# Sheet1.net
KiCad netlist of a schematic drawn in Altium Designer
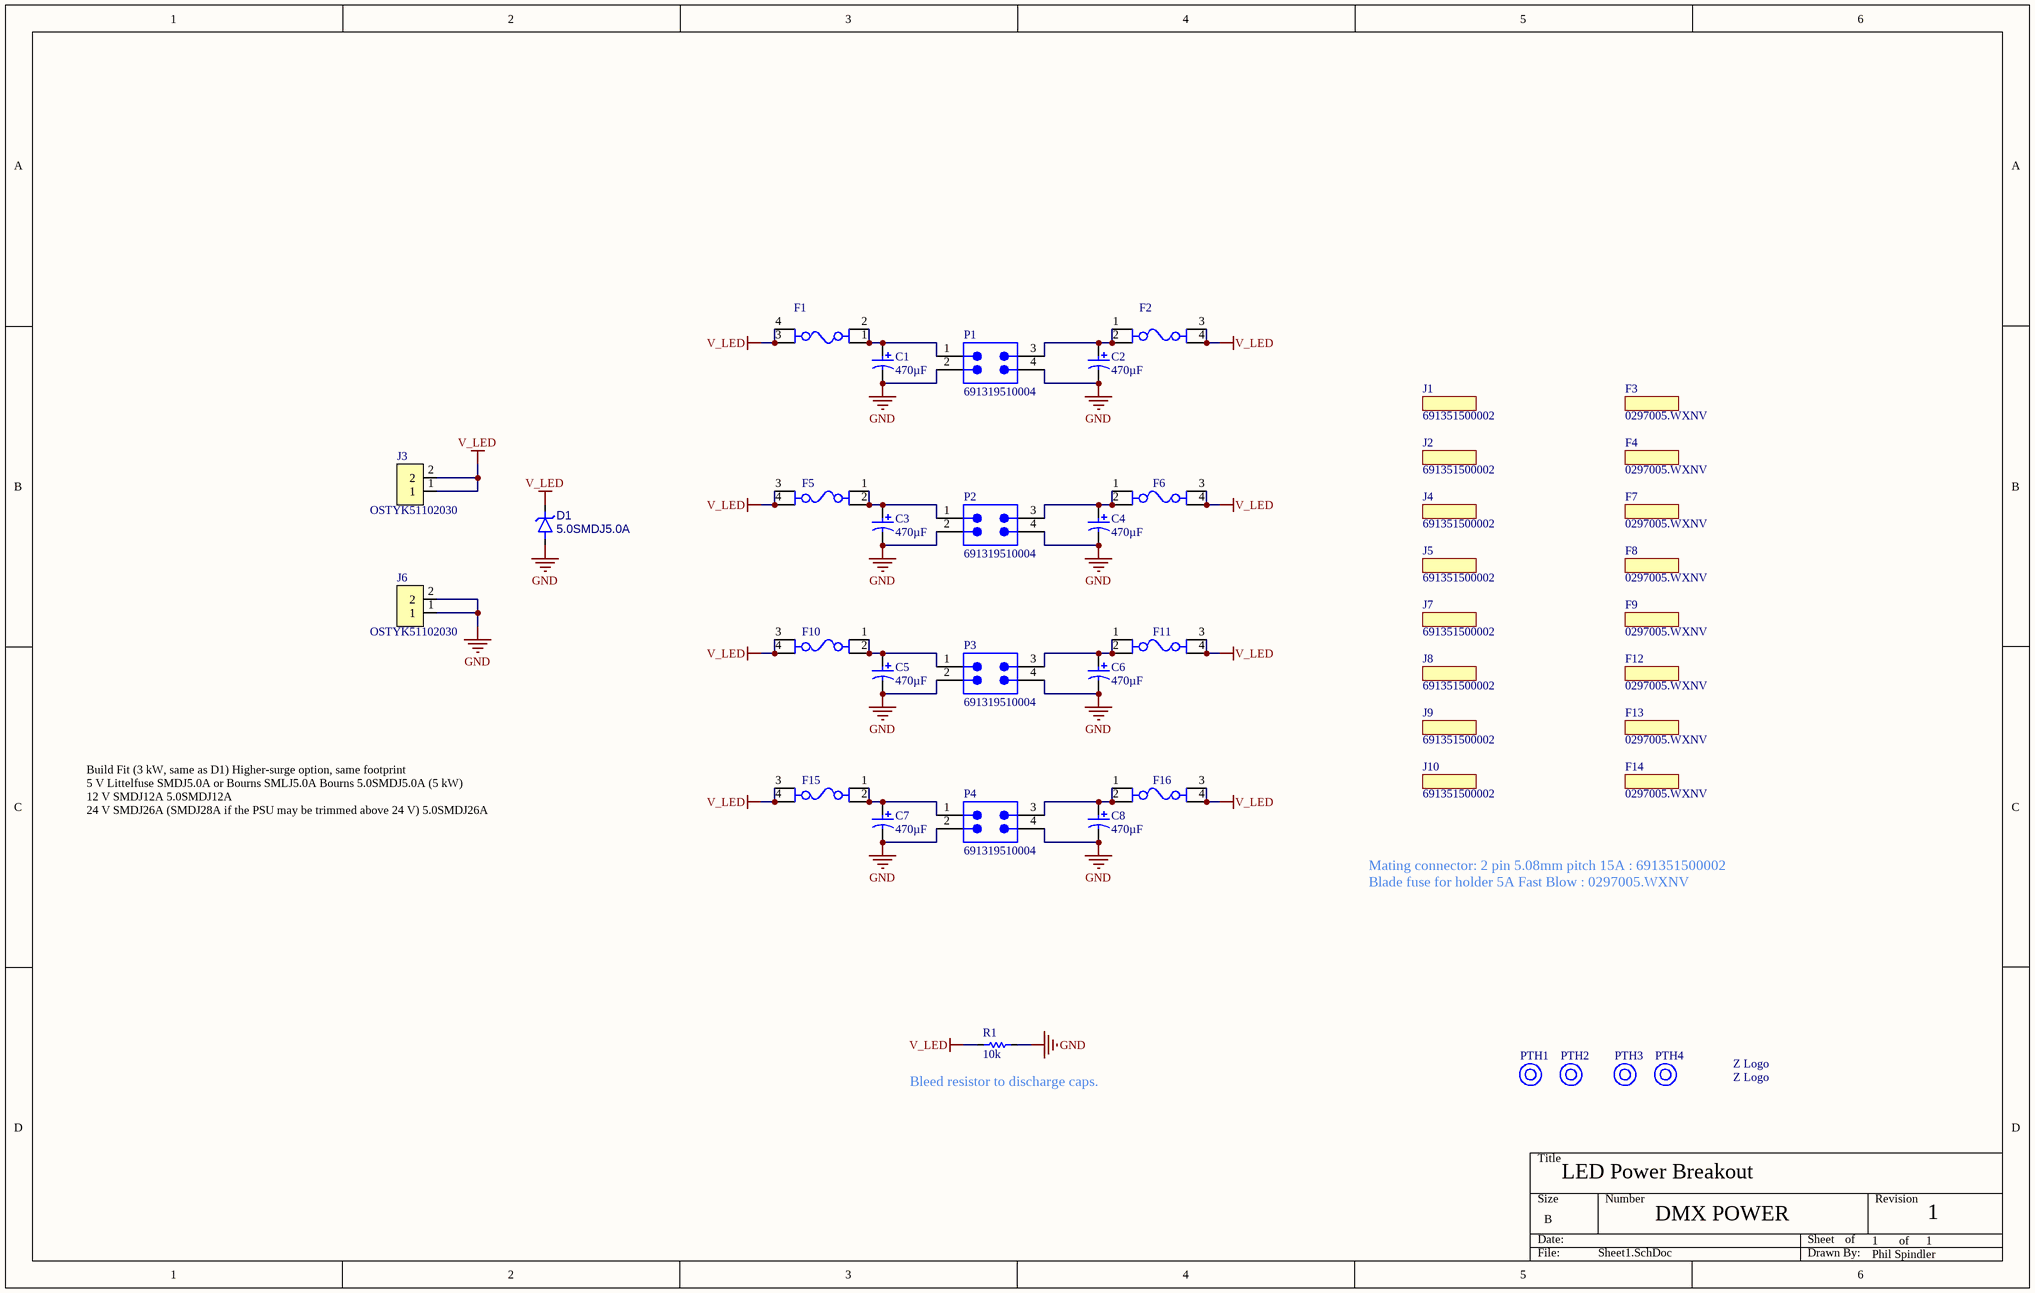
[diagram p0: Sheet1.SchDoc]

(export (version "E")
  (design (tool "Eeschema 10.0.6"))
  (components
    (comp (ref "C1")
      (value "470µF")
      (footprint "CAP_POL_DIAM10_H22_SPACING5")
      (description "CAP ALUM 470UF 20% 50V RADIAL TH")
      (fields (field (name "TOLERANCE") "20%") (field (name "Comment") "REH1020471M050K"))
      (libsource (lib "Equus Computer Systems") (part "CAP-P-2"))
    )
    (comp (ref "C2")
      (value "470µF")
      (footprint "CAP_POL_DIAM10_H22_SPACING5")
      (description "CAP ALUM 470UF 20% 50V RADIAL TH")
      (fields (field (name "TOLERANCE") "20%") (field (name "Comment") "REH1020471M050K"))
      (libsource (lib "Equus Computer Systems") (part "CAP-P-2"))
    )
    (comp (ref "C3")
      (value "470µF")
      (footprint "CAP_POL_DIAM10_H22_SPACING5")
      (description "CAP ALUM 470UF 20% 50V RADIAL TH")
      (fields (field (name "TOLERANCE") "20%") (field (name "Comment") "REH1020471M050K"))
      (libsource (lib "Equus Computer Systems") (part "CAP-P-2"))
    )
    (comp (ref "C4")
      (value "470µF")
      (footprint "CAP_POL_DIAM10_H22_SPACING5")
      (description "CAP ALUM 470UF 20% 50V RADIAL TH")
      (fields (field (name "TOLERANCE") "20%") (field (name "Comment") "REH1020471M050K"))
      (libsource (lib "Equus Computer Systems") (part "CAP-P-2"))
    )
    (comp (ref "C5")
      (value "470µF")
      (footprint "CAP_POL_DIAM10_H22_SPACING5")
      (description "CAP ALUM 470UF 20% 50V RADIAL TH")
      (fields (field (name "TOLERANCE") "20%") (field (name "Comment") "REH1020471M050K"))
      (libsource (lib "Equus Computer Systems") (part "CAP-P-2"))
    )
    (comp (ref "C6")
      (value "470µF")
      (footprint "CAP_POL_DIAM10_H22_SPACING5")
      (description "CAP ALUM 470UF 20% 50V RADIAL TH")
      (fields (field (name "TOLERANCE") "20%") (field (name "Comment") "REH1020471M050K"))
      (libsource (lib "Equus Computer Systems") (part "CAP-P-2"))
    )
    (comp (ref "C7")
      (value "470µF")
      (footprint "CAP_POL_DIAM10_H22_SPACING5")
      (description "CAP ALUM 470UF 20% 50V RADIAL TH")
      (fields (field (name "TOLERANCE") "20%") (field (name "Comment") "REH1020471M050K"))
      (libsource (lib "Equus Computer Systems") (part "CAP-P-2"))
    )
    (comp (ref "C8")
      (value "470µF")
      (footprint "CAP_POL_DIAM10_H22_SPACING5")
      (description "CAP ALUM 470UF 20% 50V RADIAL TH")
      (fields (field (name "TOLERANCE") "20%") (field (name "Comment") "REH1020471M050K"))
      (libsource (lib "Equus Computer Systems") (part "CAP-P-2"))
    )
    (comp (ref "D1")
      (value "5.0SMDJ5.0A")
      (footprint "SMDJ_DO-214AB")
      (description "5V Unidirectional 5kW TVS Diode, 9.2V Vwm, 6.4V Vbr, SMC(DO-214AB), SMD")
      (libsource (lib "Equus Computer Systems") (part "DIODE-TVS-2"))
    )
    (comp (ref "F1")
      (value "3544-2")
      (footprint "3544-2-Footprint-1")
      (description "Auto blade fuse holder; for 2.8x0.8mm mini blade fuses ATM; 20A; THT")
      (libsource (lib "Equus Computer Systems") (part "3568"))
    )
    (comp (ref "F2")
      (value "3544-2")
      (footprint "3544-2-Footprint-1")
      (description "Auto blade fuse holder; for 2.8x0.8mm mini blade fuses ATM; 20A; THT")
      (libsource (lib "Equus Computer Systems") (part "3568"))
    )
    (comp (ref "F3")
      (value "0297005.WXNV")
      (footprint "FP-0297-MFG")
      (description "Fuse Blade 5A 32V Socket 10.9 X 3.8 X 8.8mm Polyamide 66 Automotive UL")
      (libsource (lib "Equus Computer Systems") (part "MatingPartForBom"))
    )
    (comp (ref "F4")
      (value "0297005.WXNV")
      (footprint "FP-0297-MFG")
      (description "Fuse Blade 5A 32V Socket 10.9 X 3.8 X 8.8mm Polyamide 66 Automotive UL")
      (libsource (lib "Equus Computer Systems") (part "MatingPartForBom"))
    )
    (comp (ref "F5")
      (value "3544-2")
      (footprint "3544-2-Footprint-1")
      (description "Auto blade fuse holder; for 2.8x0.8mm mini blade fuses ATM; 20A; THT")
      (libsource (lib "Equus Computer Systems") (part "3568"))
    )
    (comp (ref "F6")
      (value "3544-2")
      (footprint "3544-2-Footprint-1")
      (description "Auto blade fuse holder; for 2.8x0.8mm mini blade fuses ATM; 20A; THT")
      (libsource (lib "Equus Computer Systems") (part "3568"))
    )
    (comp (ref "F7")
      (value "0297005.WXNV")
      (footprint "FP-0297-MFG")
      (description "Fuse Blade 5A 32V Socket 10.9 X 3.8 X 8.8mm Polyamide 66 Automotive UL")
      (libsource (lib "Equus Computer Systems") (part "MatingPartForBom"))
    )
    (comp (ref "F8")
      (value "0297005.WXNV")
      (footprint "FP-0297-MFG")
      (description "Fuse Blade 5A 32V Socket 10.9 X 3.8 X 8.8mm Polyamide 66 Automotive UL")
      (libsource (lib "Equus Computer Systems") (part "MatingPartForBom"))
    )
    (comp (ref "F9")
      (value "0297005.WXNV")
      (footprint "FP-0297-MFG")
      (description "Fuse Blade 5A 32V Socket 10.9 X 3.8 X 8.8mm Polyamide 66 Automotive UL")
      (libsource (lib "Equus Computer Systems") (part "MatingPartForBom"))
    )
    (comp (ref "F10")
      (value "3544-2")
      (footprint "3544-2-Footprint-1")
      (description "Auto blade fuse holder; for 2.8x0.8mm mini blade fuses ATM; 20A; THT")
      (libsource (lib "Equus Computer Systems") (part "3568"))
    )
    (comp (ref "F11")
      (value "3544-2")
      (footprint "3544-2-Footprint-1")
      (description "Auto blade fuse holder; for 2.8x0.8mm mini blade fuses ATM; 20A; THT")
      (libsource (lib "Equus Computer Systems") (part "3568"))
    )
    (comp (ref "F12")
      (value "0297005.WXNV")
      (footprint "FP-0297-MFG")
      (description "Fuse Blade 5A 32V Socket 10.9 X 3.8 X 8.8mm Polyamide 66 Automotive UL")
      (libsource (lib "Equus Computer Systems") (part "MatingPartForBom"))
    )
    (comp (ref "F13")
      (value "0297005.WXNV")
      (footprint "FP-0297-MFG")
      (description "Fuse Blade 5A 32V Socket 10.9 X 3.8 X 8.8mm Polyamide 66 Automotive UL")
      (libsource (lib "Equus Computer Systems") (part "MatingPartForBom"))
    )
    (comp (ref "F14")
      (value "0297005.WXNV")
      (footprint "FP-0297-MFG")
      (description "Fuse Blade 5A 32V Socket 10.9 X 3.8 X 8.8mm Polyamide 66 Automotive UL")
      (libsource (lib "Equus Computer Systems") (part "MatingPartForBom"))
    )
    (comp (ref "F15")
      (value "3544-2")
      (footprint "3544-2-Footprint-1")
      (description "Auto blade fuse holder; for 2.8x0.8mm mini blade fuses ATM; 20A; THT")
      (libsource (lib "Equus Computer Systems") (part "3568"))
    )
    (comp (ref "F16")
      (value "3544-2")
      (footprint "3544-2-Footprint-1")
      (description "Auto blade fuse holder; for 2.8x0.8mm mini blade fuses ATM; 20A; THT")
      (libsource (lib "Equus Computer Systems") (part "3568"))
    )
    (comp (ref "J1")
      (value "691351500002")
      (footprint "691351500002-Footprint-1")
      (description "Terminal Block, Pluggable, 2Pos, 12Awg;")
      (libsource (lib "Equus Computer Systems") (part "MatingPartForBom"))
    )
    (comp (ref "J2")
      (value "691351500002")
      (footprint "691351500002-Footprint-1")
      (description "Terminal Block, Pluggable, 2Pos, 12Awg;")
      (libsource (lib "Equus Computer Systems") (part "MatingPartForBom"))
    )
    (comp (ref "J3")
      (value "OSTYK51102030")
      (footprint "OSTYK51102030-Footprint-1")
      (description "Conn Terminal Block 2 POS 9.5mm Solder ST Thru-Hole 30A")
      (libsource (lib "Equus Computer Systems") (part "HEADER-2x1"))
    )
    (comp (ref "J4")
      (value "691351500002")
      (footprint "691351500002-Footprint-1")
      (description "Terminal Block, Pluggable, 2Pos, 12Awg;")
      (libsource (lib "Equus Computer Systems") (part "MatingPartForBom"))
    )
    (comp (ref "J5")
      (value "691351500002")
      (footprint "691351500002-Footprint-1")
      (description "Terminal Block, Pluggable, 2Pos, 12Awg;")
      (libsource (lib "Equus Computer Systems") (part "MatingPartForBom"))
    )
    (comp (ref "J6")
      (value "OSTYK51102030")
      (footprint "OSTYK51102030-Footprint-1")
      (description "Conn Terminal Block 2 POS 9.5mm Solder ST Thru-Hole 30A")
      (libsource (lib "Equus Computer Systems") (part "HEADER-2x1"))
    )
    (comp (ref "J7")
      (value "691351500002")
      (footprint "691351500002-Footprint-1")
      (description "Terminal Block, Pluggable, 2Pos, 12Awg;")
      (libsource (lib "Equus Computer Systems") (part "MatingPartForBom"))
    )
    (comp (ref "J8")
      (value "691351500002")
      (footprint "691351500002-Footprint-1")
      (description "Terminal Block, Pluggable, 2Pos, 12Awg;")
      (libsource (lib "Equus Computer Systems") (part "MatingPartForBom"))
    )
    (comp (ref "J9")
      (value "691351500002")
      (footprint "691351500002-Footprint-1")
      (description "Terminal Block, Pluggable, 2Pos, 12Awg;")
      (libsource (lib "Equus Computer Systems") (part "MatingPartForBom"))
    )
    (comp (ref "J10")
      (value "691351500002")
      (footprint "691351500002-Footprint-1")
      (description "Terminal Block, Pluggable, 2Pos, 12Awg;")
      (libsource (lib "Equus Computer Systems") (part "MatingPartForBom"))
    )
    (comp (ref "P1")
      (value "691319510004")
      (footprint "691319510004")
      (description "Terminal Block, 5.08MM, Dbl Lvl Horizontal Male Pcb Header W/closed Flange, 4PI")
      (libsource (lib "Equus Computer Systems") (part "TBL - 2R - 04P - Male"))
    )
    (comp (ref "P2")
      (value "691319510004")
      (footprint "691319510004")
      (description "Terminal Block, 5.08MM, Dbl Lvl Horizontal Male Pcb Header W/closed Flange, 4PI")
      (libsource (lib "Equus Computer Systems") (part "TBL - 2R - 04P - Male"))
    )
    (comp (ref "P3")
      (value "691319510004")
      (footprint "691319510004")
      (description "Terminal Block, 5.08MM, Dbl Lvl Horizontal Male Pcb Header W/closed Flange, 4PI")
      (libsource (lib "Equus Computer Systems") (part "TBL - 2R - 04P - Male"))
    )
    (comp (ref "P4")
      (value "691319510004")
      (footprint "691319510004")
      (description "Terminal Block, 5.08MM, Dbl Lvl Horizontal Male Pcb Header W/closed Flange, 4PI")
      (libsource (lib "Equus Computer Systems") (part "TBL - 2R - 04P - Male"))
    )
    (comp (ref "PTH1")
      (value "Mounting Hole NPTH")
      (footprint "Mounting Hole M3 No Washer NPTH")
      (libsource (lib "Equus Computer Systems") (part "Mounting Hole NPTH"))
    )
    (comp (ref "PTH2")
      (value "Mounting Hole NPTH")
      (footprint "Mounting Hole M3 No Washer NPTH")
      (libsource (lib "Equus Computer Systems") (part "Mounting Hole NPTH"))
    )
    (comp (ref "PTH3")
      (value "Mounting Hole NPTH")
      (footprint "Mounting Hole M3 No Washer NPTH")
      (libsource (lib "Equus Computer Systems") (part "Mounting Hole NPTH"))
    )
    (comp (ref "PTH4")
      (value "Mounting Hole NPTH")
      (footprint "Mounting Hole M3 No Washer NPTH")
      (libsource (lib "Equus Computer Systems") (part "Mounting Hole NPTH"))
    )
    (comp (ref "R1")
      (value "10k")
      (footprint "RESC3116X06N_1206MED")
      (fields
        (field (name "POWER") "250mW")
        (field (name "TOLERANCE") "1%")
        (field (name "Comment") "RC1206FR-0710KL")
      )
      (libsource (lib "Equus Computer Systems") (part "RES-2"))
    )
    (comp (ref "_1")
      (value "Z Logo")
      (footprint "Z Logo 0.5\"")
      (description "Z logo silkscreen")
      (libsource (lib "Equus Computer Systems") (part "Z Logo"))
    )
  )
  (nets
    (net (code "1") (name "GND") (class "Default")
      (node (ref "C1") (pin "2") (pinfunction "2_2") (pintype "passive"))
      (node (ref "C2") (pin "2") (pinfunction "2_2") (pintype "passive"))
      (node (ref "C3") (pin "2") (pinfunction "2_2") (pintype "passive"))
      (node (ref "C4") (pin "2") (pinfunction "2_2") (pintype "passive"))
      (node (ref "C5") (pin "2") (pinfunction "2_2") (pintype "passive"))
      (node (ref "C6") (pin "2") (pinfunction "2_2") (pintype "passive"))
      (node (ref "C7") (pin "2") (pinfunction "2_2") (pintype "passive"))
      (node (ref "C8") (pin "2") (pinfunction "2_2") (pintype "passive"))
      (node (ref "D1") (pin "2") (pinfunction "A_2") (pintype "passive"))
      (node (ref "J6") (pin "1") (pinfunction "1_1") (pintype "passive"))
      (node (ref "J6") (pin "2") (pinfunction "2_2") (pintype "passive"))
      (node (ref "P1") (pin "2") (pinfunction "2_2") (pintype "passive"))
      (node (ref "P1") (pin "4") (pinfunction "4_4") (pintype "passive"))
      (node (ref "P2") (pin "2") (pinfunction "2_2") (pintype "passive"))
      (node (ref "P2") (pin "4") (pinfunction "4_4") (pintype "passive"))
      (node (ref "P3") (pin "2") (pinfunction "2_2") (pintype "passive"))
      (node (ref "P3") (pin "4") (pinfunction "4_4") (pintype "passive"))
      (node (ref "P4") (pin "2") (pinfunction "2_2") (pintype "passive"))
      (node (ref "P4") (pin "4") (pinfunction "4_4") (pintype "passive"))
      (node (ref "R1") (pin "2") (pinfunction "2_2") (pintype "passive"))
    )
    (net (code "2") (name "Net-(C1-Pad1)") (class "Default")
      (node (ref "C1") (pin "1") (pinfunction "1_1") (pintype "passive"))
      (node (ref "F1") (pin "1") (pinfunction "1_1") (pintype "passive"))
      (node (ref "F1") (pin "2") (pinfunction "2_2") (pintype "passive"))
      (node (ref "P1") (pin "1") (pinfunction "1_1") (pintype "passive"))
    )
    (net (code "3") (name "Net-(C2-Pad1)") (class "Default")
      (node (ref "C2") (pin "1") (pinfunction "1_1") (pintype "passive"))
      (node (ref "F2") (pin "1") (pinfunction "1_1") (pintype "passive"))
      (node (ref "F2") (pin "2") (pinfunction "2_2") (pintype "passive"))
      (node (ref "P1") (pin "3") (pinfunction "3_3") (pintype "passive"))
    )
    (net (code "4") (name "Net-(C3-Pad1)") (class "Default")
      (node (ref "C3") (pin "1") (pinfunction "1_1") (pintype "passive"))
      (node (ref "F5") (pin "1") (pinfunction "1_1") (pintype "passive"))
      (node (ref "F5") (pin "2") (pinfunction "2_2") (pintype "passive"))
      (node (ref "P2") (pin "1") (pinfunction "1_1") (pintype "passive"))
    )
    (net (code "5") (name "Net-(C4-Pad1)") (class "Default")
      (node (ref "C4") (pin "1") (pinfunction "1_1") (pintype "passive"))
      (node (ref "F6") (pin "1") (pinfunction "1_1") (pintype "passive"))
      (node (ref "F6") (pin "2") (pinfunction "2_2") (pintype "passive"))
      (node (ref "P2") (pin "3") (pinfunction "3_3") (pintype "passive"))
    )
    (net (code "6") (name "Net-(C5-Pad1)") (class "Default")
      (node (ref "C5") (pin "1") (pinfunction "1_1") (pintype "passive"))
      (node (ref "F10") (pin "1") (pinfunction "1_1") (pintype "passive"))
      (node (ref "F10") (pin "2") (pinfunction "2_2") (pintype "passive"))
      (node (ref "P3") (pin "1") (pinfunction "1_1") (pintype "passive"))
    )
    (net (code "7") (name "Net-(C6-Pad1)") (class "Default")
      (node (ref "C6") (pin "1") (pinfunction "1_1") (pintype "passive"))
      (node (ref "F11") (pin "1") (pinfunction "1_1") (pintype "passive"))
      (node (ref "F11") (pin "2") (pinfunction "2_2") (pintype "passive"))
      (node (ref "P3") (pin "3") (pinfunction "3_3") (pintype "passive"))
    )
    (net (code "8") (name "Net-(C7-Pad1)") (class "Default")
      (node (ref "C7") (pin "1") (pinfunction "1_1") (pintype "passive"))
      (node (ref "F15") (pin "1") (pinfunction "1_1") (pintype "passive"))
      (node (ref "F15") (pin "2") (pinfunction "2_2") (pintype "passive"))
      (node (ref "P4") (pin "1") (pinfunction "1_1") (pintype "passive"))
    )
    (net (code "9") (name "Net-(C8-Pad1)") (class "Default")
      (node (ref "C8") (pin "1") (pinfunction "1_1") (pintype "passive"))
      (node (ref "F16") (pin "1") (pinfunction "1_1") (pintype "passive"))
      (node (ref "F16") (pin "2") (pinfunction "2_2") (pintype "passive"))
      (node (ref "P4") (pin "3") (pinfunction "3_3") (pintype "passive"))
    )
    (net (code "10") (name "V_LED") (class "Default")
      (node (ref "D1") (pin "1") (pinfunction "K_1") (pintype "passive"))
      (node (ref "F1") (pin "3") (pinfunction "3_3") (pintype "passive"))
      (node (ref "F1") (pin "4") (pinfunction "4_4") (pintype "passive"))
      (node (ref "F10") (pin "3") (pinfunction "3_3") (pintype "passive"))
      (node (ref "F10") (pin "4") (pinfunction "4_4") (pintype "passive"))
      (node (ref "F11") (pin "3") (pinfunction "3_3") (pintype "passive"))
      (node (ref "F11") (pin "4") (pinfunction "4_4") (pintype "passive"))
      (node (ref "F15") (pin "3") (pinfunction "3_3") (pintype "passive"))
      (node (ref "F15") (pin "4") (pinfunction "4_4") (pintype "passive"))
      (node (ref "F16") (pin "3") (pinfunction "3_3") (pintype "passive"))
      (node (ref "F16") (pin "4") (pinfunction "4_4") (pintype "passive"))
      (node (ref "F2") (pin "3") (pinfunction "3_3") (pintype "passive"))
      (node (ref "F2") (pin "4") (pinfunction "4_4") (pintype "passive"))
      (node (ref "F5") (pin "3") (pinfunction "3_3") (pintype "passive"))
      (node (ref "F5") (pin "4") (pinfunction "4_4") (pintype "passive"))
      (node (ref "F6") (pin "3") (pinfunction "3_3") (pintype "passive"))
      (node (ref "F6") (pin "4") (pinfunction "4_4") (pintype "passive"))
      (node (ref "J3") (pin "1") (pinfunction "1_1") (pintype "passive"))
      (node (ref "J3") (pin "2") (pinfunction "2_2") (pintype "passive"))
      (node (ref "R1") (pin "1") (pinfunction "1_1") (pintype "passive"))
    )
  )
)
